# FPGA_Config.net
KiCad netlist of a schematic drawn in Altium Designer
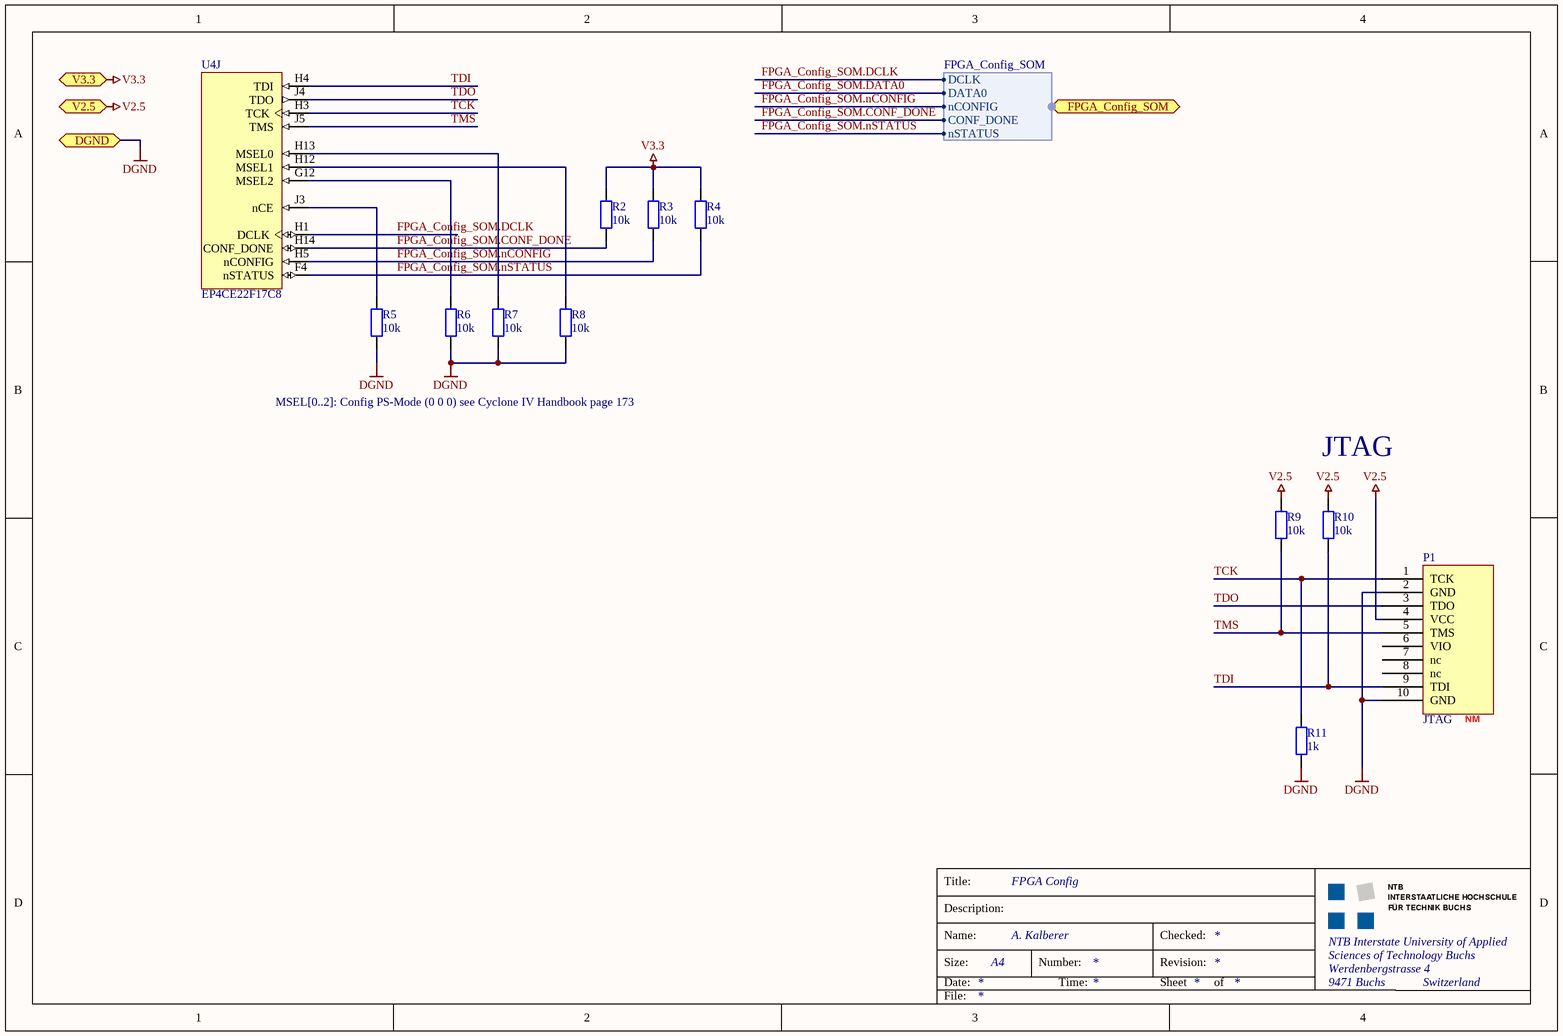
[diagram p0: FPGA_Config.SchDoc]

(export (version "E")
  (design (tool "Eeschema 10.0.6"))
  (components
    (comp (ref "P1")
      (value "JTAG")
      (footprint "Pathos:MicroMatch_10PinSMD")
      (description "Altera JTAG")
      (libsource (lib "AirBotOne") (part "AlteraJTAG"))
    )
    (comp (ref "R2")
      (value "10k")
      (footprint "Pathos:0603_3D")
      (description "Resistor")
      (fields (field (name "#PUBLISHER") "Dr. A. Heinzelmann"))
      (libsource (lib "ELE-LIB") (part "R"))
    )
    (comp (ref "R3")
      (value "10k")
      (footprint "Pathos:0603_3D")
      (description "Resistor")
      (fields (field (name "#PUBLISHER") "Dr. A. Heinzelmann"))
      (libsource (lib "ELE-LIB") (part "R"))
    )
    (comp (ref "R4")
      (value "10k")
      (footprint "Pathos:0603_3D")
      (description "Resistor")
      (fields (field (name "#PUBLISHER") "Dr. A. Heinzelmann"))
      (libsource (lib "ELE-LIB") (part "R"))
    )
    (comp (ref "R5")
      (value "10k")
      (footprint "Pathos:0603_3D")
      (description "Resistor")
      (fields (field (name "#PUBLISHER") "Dr. A. Heinzelmann"))
      (libsource (lib "ELE-LIB") (part "R"))
    )
    (comp (ref "R6")
      (value "10k")
      (footprint "Pathos:0603_3D")
      (description "Resistor")
      (fields (field (name "#PUBLISHER") "Dr. A. Heinzelmann"))
      (libsource (lib "ELE-LIB") (part "R"))
    )
    (comp (ref "R7")
      (value "10k")
      (footprint "Pathos:0603_3D")
      (description "Resistor")
      (fields (field (name "#PUBLISHER") "Dr. A. Heinzelmann"))
      (libsource (lib "ELE-LIB") (part "R"))
    )
    (comp (ref "R8")
      (value "10k")
      (footprint "Pathos:0603_3D")
      (description "Resistor")
      (fields (field (name "#PUBLISHER") "Dr. A. Heinzelmann"))
      (libsource (lib "") (part "R_1"))
    )
    (comp (ref "R9")
      (value "10k")
      (footprint "Pathos:0603_3D")
      (description "Resistor")
      (fields (field (name "#PUBLISHER") "Dr. A. Heinzelmann"))
      (libsource (lib "ELE-LIB") (part "R"))
    )
    (comp (ref "R10")
      (value "10k")
      (footprint "Pathos:0603_3D")
      (description "Resistor")
      (fields (field (name "#PUBLISHER") "Dr. A. Heinzelmann"))
      (libsource (lib "ELE-LIB") (part "R"))
    )
    (comp (ref "R11")
      (value "1k")
      (footprint "Pathos:0603_3D")
      (description "Resistor")
      (fields (field (name "#PUBLISHER") "Dr. A. Heinzelmann"))
      (libsource (lib "ELE-LIB") (part "R"))
    )
    (comp (ref "U4")
      (value "EP4CE22F17C8")
      (footprint "FBGA256")
      (fields (field (name "PUBLISHER") "Altium Limited"))
      (libsource (lib "EFS_Sensorboard") (part "EP4CE22F17C8"))
    )
  )
  (nets
    (net (code "2") (name "/FPGA_Config_SOM.CONF_DONE") (class "Default")
      (node (ref "R2") (pin "1") (pinfunction "1_1") (pintype "passive"))
      (node (ref "U4") (pin "H14") (pinfunction "CONF_DONE_H14") (pintype "bidirectional"))
    )
    (net (code "4") (name "/FPGA_Config_SOM.DCLK") (class "Default")
      (node (ref "U4") (pin "H1") (pinfunction "DCLK_H1") (pintype "bidirectional"))
    )
    (net (code "5") (name "/FPGA_Config_SOM.nCONFIG") (class "Default")
      (node (ref "R3") (pin "1") (pinfunction "1_1") (pintype "passive"))
      (node (ref "U4") (pin "H5") (pinfunction "nCONFIG_H5") (pintype "input"))
    )
    (net (code "6") (name "/FPGA_Config_SOM.nSTATUS") (class "Default")
      (node (ref "R4") (pin "1") (pinfunction "1_1") (pintype "passive"))
      (node (ref "U4") (pin "F4") (pinfunction "nSTATUS_F4") (pintype "bidirectional"))
    )
    (net (code "7") (name "/TCK") (class "Default")
      (node (ref "P1") (pin "1") (pinfunction "TCK_1") (pintype "passive"))
      (node (ref "R11") (pin "2") (pinfunction "2_2") (pintype "passive"))
      (node (ref "U4") (pin "H3") (pinfunction "TCK_H3") (pintype "input"))
    )
    (net (code "8") (name "/TDI") (class "Default")
      (node (ref "P1") (pin "9") (pinfunction "TDI_9") (pintype "passive"))
      (node (ref "R10") (pin "1") (pinfunction "1_1") (pintype "passive"))
      (node (ref "U4") (pin "H4") (pinfunction "TDI_H4") (pintype "input"))
    )
    (net (code "9") (name "/TDO") (class "Default")
      (node (ref "P1") (pin "3") (pinfunction "TDO_3") (pintype "passive"))
      (node (ref "U4") (pin "J4") (pinfunction "TDO_J4") (pintype "output"))
    )
    (net (code "10") (name "/TMS") (class "Default")
      (node (ref "P1") (pin "5") (pinfunction "TMS_5") (pintype "passive"))
      (node (ref "R9") (pin "1") (pinfunction "1_1") (pintype "passive"))
      (node (ref "U4") (pin "J5") (pinfunction "TMS_J5") (pintype "input"))
    )
    (net (code "12") (name "DGND") (class "Default")
      (node (ref "P1") (pin "10") (pinfunction "GND_10") (pintype "passive"))
      (node (ref "P1") (pin "2") (pinfunction "GND_2") (pintype "passive"))
      (node (ref "R11") (pin "1") (pinfunction "1_1") (pintype "passive"))
      (node (ref "R5") (pin "1") (pinfunction "1_1") (pintype "passive"))
      (node (ref "R6") (pin "1") (pinfunction "1_1") (pintype "passive"))
      (node (ref "R7") (pin "1") (pinfunction "1_1") (pintype "passive"))
      (node (ref "R8") (pin "2") (pinfunction "2_2") (pintype "passive"))
    )
    (net (code "13") (name "Net-(U4J-MSEL0)") (class "Default")
      (node (ref "R7") (pin "2") (pinfunction "2_2") (pintype "passive"))
      (node (ref "U4") (pin "H13") (pinfunction "MSEL0_H13") (pintype "input"))
    )
    (net (code "14") (name "Net-(U4J-MSEL1)") (class "Default")
      (node (ref "R8") (pin "1") (pinfunction "1_1") (pintype "passive"))
      (node (ref "U4") (pin "H12") (pinfunction "MSEL1_H12") (pintype "input"))
    )
    (net (code "15") (name "Net-(U4J-MSEL2)") (class "Default")
      (node (ref "R6") (pin "2") (pinfunction "2_2") (pintype "passive"))
      (node (ref "U4") (pin "G12") (pinfunction "MSEL2_G12") (pintype "input"))
    )
    (net (code "16") (name "Net-(U4J-nCE)") (class "Default")
      (node (ref "R5") (pin "2") (pinfunction "2_2") (pintype "passive"))
      (node (ref "U4") (pin "J3") (pinfunction "nCE_J3") (pintype "input"))
    )
    (net (code "17") (name "V2.5") (class "Default")
      (node (ref "P1") (pin "4") (pinfunction "VCC_4") (pintype "passive"))
      (node (ref "R10") (pin "2") (pinfunction "2_2") (pintype "passive"))
      (node (ref "R9") (pin "2") (pinfunction "2_2") (pintype "passive"))
    )
    (net (code "18") (name "V3.3") (class "Default")
      (node (ref "R2") (pin "2") (pinfunction "2_2") (pintype "passive"))
      (node (ref "R3") (pin "2") (pinfunction "2_2") (pintype "passive"))
      (node (ref "R4") (pin "2") (pinfunction "2_2") (pintype "passive"))
    )
    (net (code "19") (name "unconnected-(P1-VIO-Pad6)") (class "Default")
      (node (ref "P1") (pin "6") (pinfunction "VIO_6") (pintype "passive"))
    )
    (net (code "20") (name "unconnected-(P1-nc-Pad7)") (class "Default")
      (node (ref "P1") (pin "7") (pinfunction "nc_7") (pintype "passive"))
    )
    (net (code "21") (name "unconnected-(P1-nc-Pad8)") (class "Default")
      (node (ref "P1") (pin "8") (pinfunction "nc_8") (pintype "passive"))
    )
  )
)
